# Led_Driver_27V.net
KiCad netlist of a schematic drawn in EAGLE
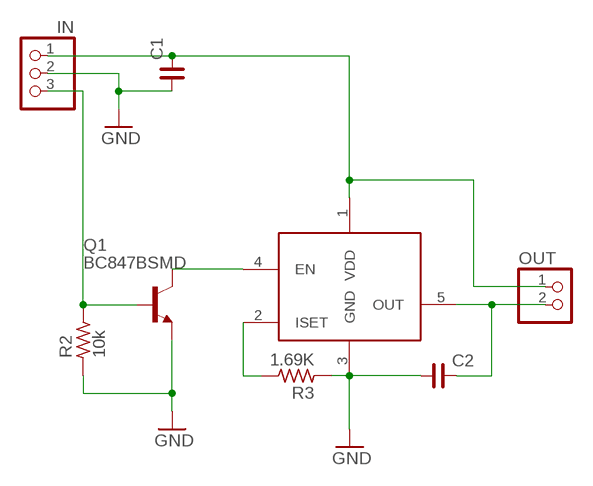
[diagram p0: schematic, sheet 1]

(export (version "E")
  (design (tool "Eeschema 10.0.6"))
  (components
    (comp (ref "C1")
      (value "C_0603")
      (footprint "eagle-import:C0603")
      (libsource (lib "eagle-import") (part "C_0603"))
    )
    (comp (ref "C2")
      (value "C_0603")
      (footprint "eagle-import:C0603")
      (libsource (lib "eagle-import") (part "C_0603"))
    )
    (comp (ref "IN")
      (value "PINHD-1X03_2.54-S")
      (footprint "eagle-import:1X03-S")
      (libsource (lib "eagle-import") (part "PINHD-1X03_2.54-S"))
    )
    (comp (ref "OUT")
      (value "PINHD-1X02_2.54-S")
      (footprint "eagle-import:1X02-S")
      (libsource (lib "eagle-import") (part "PINHD-1X02_2.54-S"))
    )
    (comp (ref "Q1")
      (value "BC847BSMD")
      (footprint "eagle-import:SOT23")
      (libsource (lib "eagle-import") (part "BC847SMDB"))
    )
    (comp (ref "R2")
      (value "10k")
      (footprint "eagle-import:R1206")
      (libsource (lib "eagle-import") (part "R_1206"))
    )
    (comp (ref "R3")
      (value "1.69K")
      (footprint "eagle-import:R1206")
      (libsource (lib "eagle-import") (part "R_1206"))
    )
    (comp (ref "U$1")
      (value "AMC7140")
      (footprint "eagle-import:TO252-5L")
      (libsource (lib "eagle-import") (part "AMC7140"))
    )
  )
  (nets
    (net (code "1") (name "GND") (class "Default")
      (node (ref "C1") (pin "1") (pinfunction "1_1") (pintype "passive"))
      (node (ref "C2") (pin "1") (pinfunction "1_1") (pintype "passive"))
      (node (ref "IN") (pin "2") (pinfunction "2_2") (pintype "passive"))
      (node (ref "Q1") (pin "2") (pinfunction "E_2") (pintype "passive"))
      (node (ref "R2") (pin "1") (pinfunction "1_1") (pintype "passive"))
      (node (ref "R3") (pin "1") (pinfunction "1_1") (pintype "passive"))
      (node (ref "U$1") (pin "3") (pinfunction "GND_3") (pintype "power_in"))
    )
    (net (code "2") (name "Net-(Q1-B)") (class "Default")
      (node (ref "IN") (pin "3") (pinfunction "3_3") (pintype "passive"))
      (node (ref "Q1") (pin "1") (pinfunction "B_1") (pintype "passive"))
      (node (ref "R2") (pin "2") (pinfunction "2_2") (pintype "passive"))
    )
    (net (code "3") (name "Net-(Q1-C)") (class "Default")
      (node (ref "Q1") (pin "3") (pinfunction "C_3") (pintype "passive"))
      (node (ref "U$1") (pin "4") (pinfunction "EN_4") (pintype "input"))
    )
    (net (code "4") (name "Net-(U$1-ISET)") (class "Default")
      (node (ref "R3") (pin "2") (pinfunction "2_2") (pintype "passive"))
      (node (ref "U$1") (pin "2") (pinfunction "ISET_2") (pintype "power_in"))
    )
    (net (code "5") (name "Net-(U$1-OUT)") (class "Default")
      (node (ref "C2") (pin "2") (pinfunction "2_2") (pintype "passive"))
      (node (ref "OUT") (pin "2") (pinfunction "2_2") (pintype "passive"))
      (node (ref "U$1") (pin "5") (pinfunction "OUT_5") (pintype "output"))
    )
    (net (code "6") (name "Net-(U$1-VDD)") (class "Default")
      (node (ref "C1") (pin "2") (pinfunction "2_2") (pintype "passive"))
      (node (ref "IN") (pin "1") (pinfunction "1_1") (pintype "passive"))
      (node (ref "OUT") (pin "1") (pinfunction "1_1") (pintype "passive"))
      (node (ref "U$1") (pin "1") (pinfunction "VDD_1") (pintype "power_in"))
    )
  )
)
